# in3brain.net
KiCad netlist of a schematic drawn in EAGLE
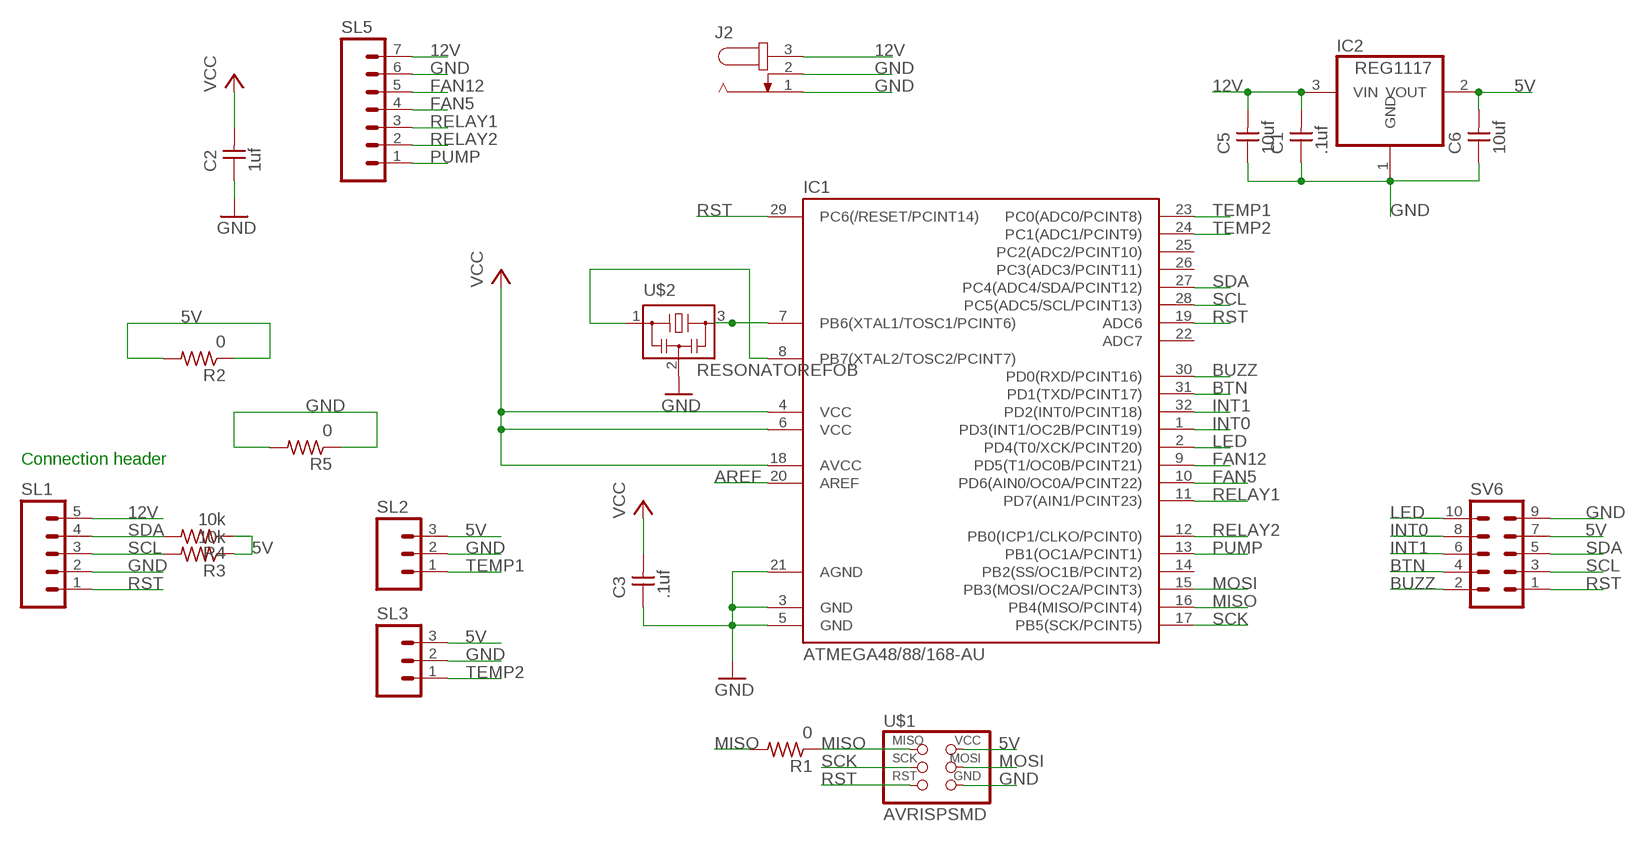
[diagram p0: schematic, sheet 1]

(export (version "E")
  (design (tool "Eeschema 10.0.6"))
  (components
    (comp (ref "C1")
      (value ".1uf")
      (footprint "eagle-import:1206")
      (libsource (lib "eagle-import") (part "UNPOLARIZED_CAPACITOR1206"))
    )
    (comp (ref "C2")
      (value "1uf")
      (footprint "eagle-import:1206")
      (libsource (lib "eagle-import") (part "UNPOLARIZED_CAPACITOR1206"))
    )
    (comp (ref "C3")
      (value ".1uf")
      (footprint "eagle-import:1206")
      (libsource (lib "eagle-import") (part "UNPOLARIZED_CAPACITOR1206"))
    )
    (comp (ref "C5")
      (value "10uf")
      (footprint "eagle-import:1206")
      (libsource (lib "eagle-import") (part "UNPOLARIZED_CAPACITOR1206"))
    )
    (comp (ref "C6")
      (value "10uf")
      (footprint "eagle-import:1206")
      (libsource (lib "eagle-import") (part "UNPOLARIZED_CAPACITOR1206"))
    )
    (comp (ref "IC1")
      (value "ATMEGA48/88/168-AU")
      (footprint "eagle-import:TQFP32-08")
      (libsource (lib "eagle-import") (part "ATMEGA48/88/168-AU"))
    )
    (comp (ref "IC2")
      (value "REG1117")
      (footprint "eagle-import:SOT223")
      (libsource (lib "eagle-import") (part "REG1117"))
    )
    (comp (ref "J2")
      (value "JACK-PLUG1")
      (footprint "eagle-import:SPC4078")
      (libsource (lib "eagle-import") (part "JACK-PLUG1"))
    )
    (comp (ref "R1")
      (value "0")
      (footprint "eagle-import:1206")
      (libsource (lib "eagle-import") (part "RESISTOR1206"))
    )
    (comp (ref "R2")
      (value "0")
      (footprint "eagle-import:1206")
      (libsource (lib "eagle-import") (part "RESISTOR1206"))
    )
    (comp (ref "R3")
      (value "10k")
      (footprint "eagle-import:1206")
      (libsource (lib "eagle-import") (part "RESISTOR1206"))
    )
    (comp (ref "R4")
      (value "10k")
      (footprint "eagle-import:1206")
      (libsource (lib "eagle-import") (part "RESISTOR1206"))
    )
    (comp (ref "R5")
      (value "0")
      (footprint "eagle-import:1206")
      (libsource (lib "eagle-import") (part "RESISTOR1206"))
    )
    (comp (ref "SL1")
      (value "MA05")
      (footprint "eagle-import:05PA")
      (libsource (lib "eagle-import") (part "MA05"))
    )
    (comp (ref "SL2")
      (value "MA03")
      (footprint "eagle-import:03P")
      (libsource (lib "eagle-import") (part "MA03"))
    )
    (comp (ref "SL3")
      (value "MA03")
      (footprint "eagle-import:03P")
      (libsource (lib "eagle-import") (part "MA03"))
    )
    (comp (ref "SL5")
      (value "MA07")
      (footprint "eagle-import:07PA")
      (libsource (lib "eagle-import") (part "MA07"))
    )
    (comp (ref "SV6")
      (value "MA05-2")
      (footprint "eagle-import:MA05-2")
      (libsource (lib "eagle-import") (part "MA05-2"))
    )
    (comp (ref "U$1")
      (value "AVRISPSMD")
      (footprint "eagle-import:2X03SMD")
      (libsource (lib "eagle-import") (part "AVRISPSMD"))
    )
    (comp (ref "U$2")
      (value "RESONATOREFOB")
      (footprint "eagle-import:EFOBM")
      (libsource (lib "eagle-import") (part "RESONATOREFOB"))
    )
  )
  (nets
    (net (code "1") (name "/12V") (class "Default")
      (node (ref "C1") (pin "2") (pinfunction "2_2") (pintype "passive"))
      (node (ref "C5") (pin "2") (pinfunction "2_2") (pintype "passive"))
      (node (ref "IC2") (pin "3") (pinfunction "VIN_3") (pintype "input"))
      (node (ref "J2") (pin "3") (pinfunction "3_3") (pintype "passive"))
      (node (ref "SL1") (pin "5") (pinfunction "5_5") (pintype "passive"))
      (node (ref "SL5") (pin "7") (pinfunction "7_7") (pintype "passive"))
    )
    (net (code "2") (name "/AREF") (class "Default")
      (node (ref "IC1") (pin "20") (pinfunction "AREF_20") (pintype "passive"))
    )
    (net (code "3") (name "/BTN") (class "Default")
      (node (ref "IC1") (pin "31") (pinfunction "PD1(TXD/PCINT17)_31") (pintype "bidirectional"))
      (node (ref "SV6") (pin "4") (pinfunction "4_4") (pintype "passive"))
    )
    (net (code "4") (name "/BUZZ") (class "Default")
      (node (ref "IC1") (pin "30") (pinfunction "PD0(RXD/PCINT16)_30") (pintype "bidirectional"))
      (node (ref "SV6") (pin "2") (pinfunction "2_2") (pintype "passive"))
    )
    (net (code "5") (name "/FAN5") (class "Default")
      (node (ref "IC1") (pin "10") (pinfunction "PD6(AIN0/OC0A/PCINT22)_10") (pintype "bidirectional"))
      (node (ref "SL5") (pin "4") (pinfunction "4_4") (pintype "passive"))
    )
    (net (code "6") (name "/FAN12") (class "Default")
      (node (ref "IC1") (pin "9") (pinfunction "PD5(T1/OC0B/PCINT21)_9") (pintype "bidirectional"))
      (node (ref "SL5") (pin "5") (pinfunction "5_5") (pintype "passive"))
    )
    (net (code "7") (name "/INT0") (class "Default")
      (node (ref "IC1") (pin "1") (pinfunction "PD3(INT1/OC2B/PCINT19)_1") (pintype "bidirectional"))
      (node (ref "SV6") (pin "8") (pinfunction "8_8") (pintype "passive"))
    )
    (net (code "8") (name "/INT1") (class "Default")
      (node (ref "IC1") (pin "32") (pinfunction "PD2(INT0/PCINT18)_32") (pintype "bidirectional"))
      (node (ref "SV6") (pin "6") (pinfunction "6_6") (pintype "passive"))
    )
    (net (code "9") (name "/LED") (class "Default")
      (node (ref "IC1") (pin "2") (pinfunction "PD4(T0/XCK/PCINT20)_2") (pintype "bidirectional"))
      (node (ref "SV6") (pin "10") (pinfunction "10_10") (pintype "passive"))
    )
    (net (code "10") (name "/MISO") (class "Default")
      (node (ref "IC1") (pin "16") (pinfunction "PB4(MISO/PCINT4)_16") (pintype "bidirectional"))
      (node (ref "R1") (pin "1") (pinfunction "1_1") (pintype "passive"))
      (node (ref "R1") (pin "2") (pinfunction "2_2") (pintype "passive"))
      (node (ref "U$1") (pin "1") (pinfunction "MISO_1") (pintype "passive"))
    )
    (net (code "11") (name "/MOSI") (class "Default")
      (node (ref "IC1") (pin "15") (pinfunction "PB3(MOSI/OC2A/PCINT3)_15") (pintype "bidirectional"))
      (node (ref "U$1") (pin "4") (pinfunction "MOSI_4") (pintype "passive"))
    )
    (net (code "12") (name "/PUMP") (class "Default")
      (node (ref "IC1") (pin "13") (pinfunction "PB1(OC1A/PCINT1)_13") (pintype "bidirectional"))
      (node (ref "SL5") (pin "1") (pinfunction "1_1") (pintype "passive"))
    )
    (net (code "13") (name "/RELAY1") (class "Default")
      (node (ref "IC1") (pin "11") (pinfunction "PD7(AIN1/PCINT23)_11") (pintype "bidirectional"))
      (node (ref "SL5") (pin "3") (pinfunction "3_3") (pintype "passive"))
    )
    (net (code "14") (name "/RELAY2") (class "Default")
      (node (ref "IC1") (pin "12") (pinfunction "PB0(ICP1/CLKO/PCINT0)_12") (pintype "bidirectional"))
      (node (ref "SL5") (pin "2") (pinfunction "2_2") (pintype "passive"))
    )
    (net (code "15") (name "/RST") (class "Default")
      (node (ref "IC1") (pin "19") (pinfunction "ADC6_19") (pintype "passive"))
      (node (ref "IC1") (pin "29") (pinfunction "PC6(/RESET/PCINT14)_29") (pintype "bidirectional"))
      (node (ref "SL1") (pin "1") (pinfunction "1_1") (pintype "passive"))
      (node (ref "SV6") (pin "1") (pinfunction "1_1") (pintype "passive"))
      (node (ref "U$1") (pin "5") (pinfunction "RST_5") (pintype "passive"))
    )
    (net (code "16") (name "/SCK") (class "Default")
      (node (ref "IC1") (pin "17") (pinfunction "PB5(SCK/PCINT5)_17") (pintype "bidirectional"))
      (node (ref "U$1") (pin "3") (pinfunction "SCK_3") (pintype "passive"))
    )
    (net (code "17") (name "/SCL") (class "Default")
      (node (ref "IC1") (pin "28") (pinfunction "PC5(ADC5/SCL/PCINT13)_28") (pintype "bidirectional"))
      (node (ref "R3") (pin "2") (pinfunction "2_2") (pintype "passive"))
      (node (ref "SL1") (pin "3") (pinfunction "3_3") (pintype "passive"))
      (node (ref "SV6") (pin "3") (pinfunction "3_3") (pintype "passive"))
    )
    (net (code "18") (name "/SDA") (class "Default")
      (node (ref "IC1") (pin "27") (pinfunction "PC4(ADC4/SDA/PCINT12)_27") (pintype "bidirectional"))
      (node (ref "R4") (pin "2") (pinfunction "2_2") (pintype "passive"))
      (node (ref "SL1") (pin "4") (pinfunction "4_4") (pintype "passive"))
      (node (ref "SV6") (pin "5") (pinfunction "5_5") (pintype "passive"))
    )
    (net (code "19") (name "/TEMP1") (class "Default")
      (node (ref "IC1") (pin "23") (pinfunction "PC0(ADC0/PCINT8)_23") (pintype "bidirectional"))
      (node (ref "SL2") (pin "1") (pinfunction "1_1") (pintype "passive"))
    )
    (net (code "20") (name "/TEMP2") (class "Default")
      (node (ref "IC1") (pin "24") (pinfunction "PC1(ADC1/PCINT9)_24") (pintype "bidirectional"))
      (node (ref "SL3") (pin "1") (pinfunction "1_1") (pintype "passive"))
    )
    (net (code "21") (name "GND") (class "Default")
      (node (ref "C1") (pin "1") (pinfunction "1_1") (pintype "passive"))
      (node (ref "C2") (pin "1") (pinfunction "1_1") (pintype "passive"))
      (node (ref "C3") (pin "1") (pinfunction "1_1") (pintype "passive"))
      (node (ref "C5") (pin "1") (pinfunction "1_1") (pintype "passive"))
      (node (ref "C6") (pin "1") (pinfunction "1_1") (pintype "passive"))
      (node (ref "IC1") (pin "21") (pinfunction "AGND_21") (pintype "power_in"))
      (node (ref "IC1") (pin "3") (pinfunction "GND_3") (pintype "power_in"))
      (node (ref "IC1") (pin "5") (pinfunction "GND_5") (pintype "power_in"))
      (node (ref "IC2") (pin "1") (pinfunction "GND_1") (pintype "power_in"))
      (node (ref "J2") (pin "1") (pinfunction "1_1") (pintype "passive"))
      (node (ref "J2") (pin "2") (pinfunction "2_2") (pintype "passive"))
      (node (ref "R5") (pin "1") (pinfunction "1_1") (pintype "passive"))
      (node (ref "R5") (pin "2") (pinfunction "2_2") (pintype "passive"))
      (node (ref "SL1") (pin "2") (pinfunction "2_2") (pintype "passive"))
      (node (ref "SL2") (pin "2") (pinfunction "2_2") (pintype "passive"))
      (node (ref "SL3") (pin "2") (pinfunction "2_2") (pintype "passive"))
      (node (ref "SL5") (pin "6") (pinfunction "6_6") (pintype "passive"))
      (node (ref "SV6") (pin "9") (pinfunction "9_9") (pintype "passive"))
      (node (ref "U$1") (pin "6") (pinfunction "GND_6") (pintype "passive"))
      (node (ref "U$2") (pin "2") (pinfunction "2_2") (pintype "passive"))
    )
    (net (code "22") (name "Net-(IC1-PB6(XTAL1{slash}TOSC1{slash}PCINT6))") (class "Default")
      (node (ref "IC1") (pin "7") (pinfunction "PB6(XTAL1/TOSC1/PCINT6)_7") (pintype "bidirectional"))
      (node (ref "U$2") (pin "3") (pinfunction "3_3") (pintype "passive"))
    )
    (net (code "23") (name "Net-(IC1-PB7(XTAL2{slash}TOSC2{slash}PCINT7))") (class "Default")
      (node (ref "IC1") (pin "8") (pinfunction "PB7(XTAL2/TOSC2/PCINT7)_8") (pintype "bidirectional"))
      (node (ref "U$2") (pin "1") (pinfunction "1_1") (pintype "passive"))
    )
    (net (code "24") (name "VCC") (class "Default")
      (node (ref "C2") (pin "2") (pinfunction "2_2") (pintype "passive"))
      (node (ref "C3") (pin "2") (pinfunction "2_2") (pintype "passive"))
      (node (ref "C6") (pin "2") (pinfunction "2_2") (pintype "passive"))
      (node (ref "IC1") (pin "18") (pinfunction "AVCC_18") (pintype "passive"))
      (node (ref "IC1") (pin "4") (pinfunction "VCC_4") (pintype "power_in"))
      (node (ref "IC1") (pin "6") (pinfunction "VCC_6") (pintype "power_in"))
      (node (ref "IC2") (pin "2") (pinfunction "VOUT_2") (pintype "output"))
      (node (ref "R2") (pin "1") (pinfunction "1_1") (pintype "passive"))
      (node (ref "R2") (pin "2") (pinfunction "2_2") (pintype "passive"))
      (node (ref "R3") (pin "1") (pinfunction "1_1") (pintype "passive"))
      (node (ref "R4") (pin "1") (pinfunction "1_1") (pintype "passive"))
      (node (ref "SL2") (pin "3") (pinfunction "3_3") (pintype "passive"))
      (node (ref "SL3") (pin "3") (pinfunction "3_3") (pintype "passive"))
      (node (ref "SV6") (pin "7") (pinfunction "7_7") (pintype "passive"))
      (node (ref "U$1") (pin "2") (pinfunction "VCC_2") (pintype "passive"))
    )
    (net (code "25") (name "unconnected-(IC1-ADC7-Pad22)") (class "Default")
      (node (ref "IC1") (pin "22") (pinfunction "ADC7_22") (pintype "passive"))
    )
    (net (code "26") (name "unconnected-(IC1-PB2(SS{slash}OC1B{slash}PCINT2)-Pad14)") (class "Default")
      (node (ref "IC1") (pin "14") (pinfunction "PB2(SS/OC1B/PCINT2)_14") (pintype "bidirectional"))
    )
    (net (code "27") (name "unconnected-(IC1-PC2(ADC2{slash}PCINT10)-Pad25)") (class "Default")
      (node (ref "IC1") (pin "25") (pinfunction "PC2(ADC2/PCINT10)_25") (pintype "bidirectional"))
    )
    (net (code "28") (name "unconnected-(IC1-PC3(ADC3{slash}PCINT11)-Pad26)") (class "Default")
      (node (ref "IC1") (pin "26") (pinfunction "PC3(ADC3/PCINT11)_26") (pintype "bidirectional"))
    )
  )
)
